# 230V_AC_Switch.net
KiCad netlist of a schematic drawn in EAGLE
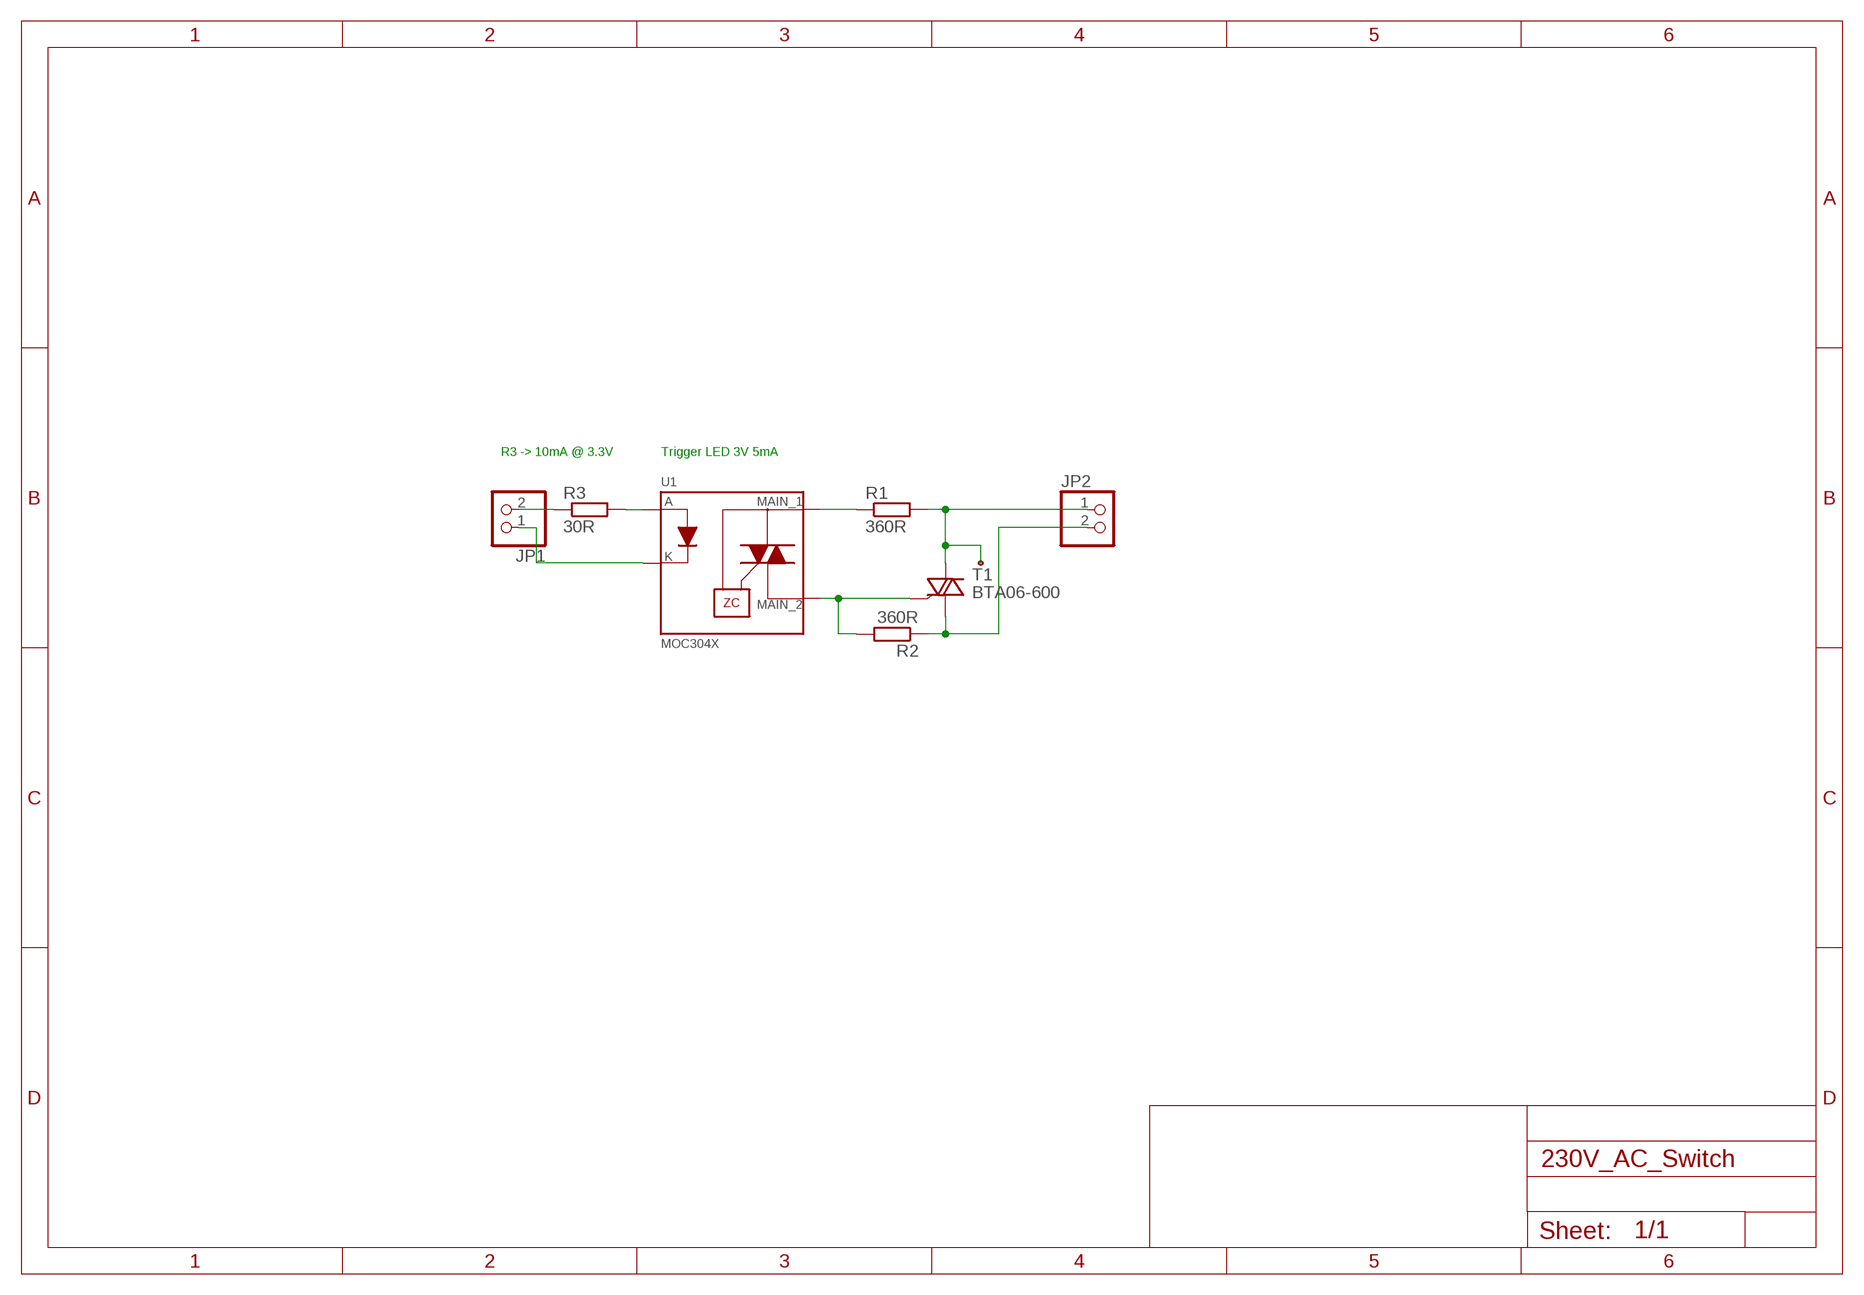
[diagram p0: schematic, sheet 1]

(export (version "E")
  (design (tool "Eeschema 10.0.6"))
  (components
    (comp (ref "JP1")
      (value "PINHD-1X2")
      (footprint "eagle-import:1X02")
      (libsource (lib "eagle-import") (part "PINHD-1X2"))
    )
    (comp (ref "JP2")
      (value "PINHD-1X2")
      (footprint "eagle-import:1X02")
      (libsource (lib "eagle-import") (part "PINHD-1X2"))
    )
    (comp (ref "R1")
      (value "360R")
      (footprint "eagle-import:R1206")
      (libsource (lib "eagle-import") (part "R-EU_R1206"))
    )
    (comp (ref "R2")
      (value "360R")
      (footprint "eagle-import:R1206")
      (libsource (lib "eagle-import") (part "R-EU_R1206"))
    )
    (comp (ref "R3")
      (value "30R")
      (footprint "eagle-import:R0603")
      (libsource (lib "eagle-import") (part "R-EU_R0603"))
    )
    (comp (ref "T1")
      (value "BTA06-600")
      (footprint "eagle-import:TO220AB")
      (libsource (lib "eagle-import") (part "BTA06-600"))
    )
    (comp (ref "U1")
      (value "MOC304X")
      (footprint "eagle-import:PDIP")
      (libsource (lib "eagle-import") (part "MOC304X"))
    )
  )
  (nets
    (net (code "1") (name "Net-(JP1-Pad2)") (class "Default")
      (node (ref "JP1") (pin "2") (pinfunction "2_2") (pintype "passive"))
      (node (ref "R3") (pin "1") (pinfunction "1_1") (pintype "passive"))
    )
    (net (code "2") (name "Net-(T1-A1)") (class "Default")
      (node (ref "JP2") (pin "2") (pinfunction "2_2") (pintype "passive"))
      (node (ref "R2") (pin "1") (pinfunction "1_1") (pintype "passive"))
      (node (ref "T1") (pin "1") (pinfunction "A1_1") (pintype "passive"))
    )
    (net (code "3") (name "Net-(T1-A2)") (class "Default")
      (node (ref "JP2") (pin "1") (pinfunction "1_1") (pintype "passive"))
      (node (ref "R1") (pin "2") (pinfunction "2_2") (pintype "passive"))
      (node (ref "T1") (pin "2") (pinfunction "A2_2") (pintype "passive"))
      (node (ref "T1") (pin "PAD") (pinfunction "PAD_PAD") (pintype "passive"))
    )
    (net (code "4") (name "Net-(T1-G)") (class "Default")
      (node (ref "R2") (pin "2") (pinfunction "2_2") (pintype "passive"))
      (node (ref "T1") (pin "3") (pinfunction "G_3") (pintype "passive"))
      (node (ref "U1") (pin "4") (pinfunction "MAIN_2_4") (pintype "bidirectional"))
    )
    (net (code "5") (name "Net-(U1-A)") (class "Default")
      (node (ref "R3") (pin "2") (pinfunction "2_2") (pintype "passive"))
      (node (ref "U1") (pin "1") (pinfunction "A_1") (pintype "bidirectional"))
    )
    (net (code "6") (name "Net-(U1-K)") (class "Default")
      (node (ref "JP1") (pin "1") (pinfunction "1_1") (pintype "passive"))
      (node (ref "U1") (pin "2") (pinfunction "K_2") (pintype "bidirectional"))
    )
    (net (code "7") (name "Net-(U1-MAIN_1)") (class "Default")
      (node (ref "R1") (pin "1") (pinfunction "1_1") (pintype "passive"))
      (node (ref "U1") (pin "6") (pinfunction "MAIN_1_6") (pintype "bidirectional"))
    )
  )
)
